# power.net
KiCad netlist of a schematic drawn in Altium Designer
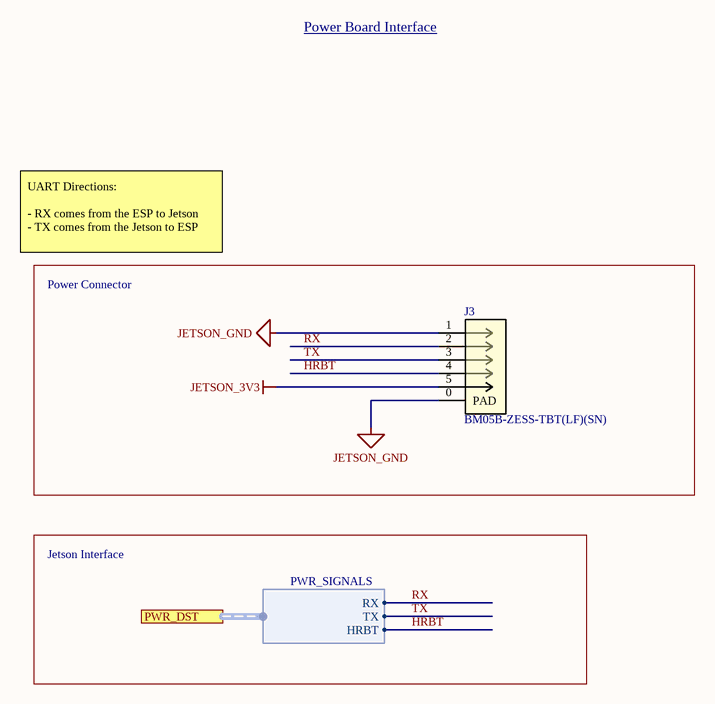
[diagram p0: power.SchDoc]

(export (version "E")
  (design (tool "Eeschema 10.0.6"))
  (components
    (comp (ref "J3")
      (value "BM05B-ZESS-TBT(LF)(SN)")
      (footprint "JST ZE SMT 5POS")
      (description "CONN HEADER VERT SMD 5POS ZE")
      (fields (field (name "PART NUMBER") "CN 5POS JST ZE SMT"))
      (libsource (lib "Connector_Library") (part "CN 5POS JST ZE SMT"))
    )
  )
  (nets
    (net (code "3") (name "/HRBT") (class "Default")
      (node (ref "J3") (pin "4") (pinfunction "4_4") (pintype "passive"))
    )
    (net (code "4") (name "/RX") (class "Default")
      (node (ref "J3") (pin "2") (pinfunction "2_2") (pintype "passive"))
    )
    (net (code "5") (name "/TX") (class "Default")
      (node (ref "J3") (pin "3") (pinfunction "3_3") (pintype "passive"))
    )
    (net (code "7") (name "JETSON_3V3") (class "Default")
      (node (ref "J3") (pin "5") (pinfunction "5_5") (pintype "passive"))
    )
    (net (code "8") (name "JETSON_GND") (class "Default")
      (node (ref "J3") (pin "0") (pinfunction "PAD_0") (pintype "passive"))
      (node (ref "J3") (pin "1") (pinfunction "1_1") (pintype "passive"))
    )
  )
)
